# Vorlage_ATmega644PA.net
KiCad netlist of a schematic drawn in EAGLE
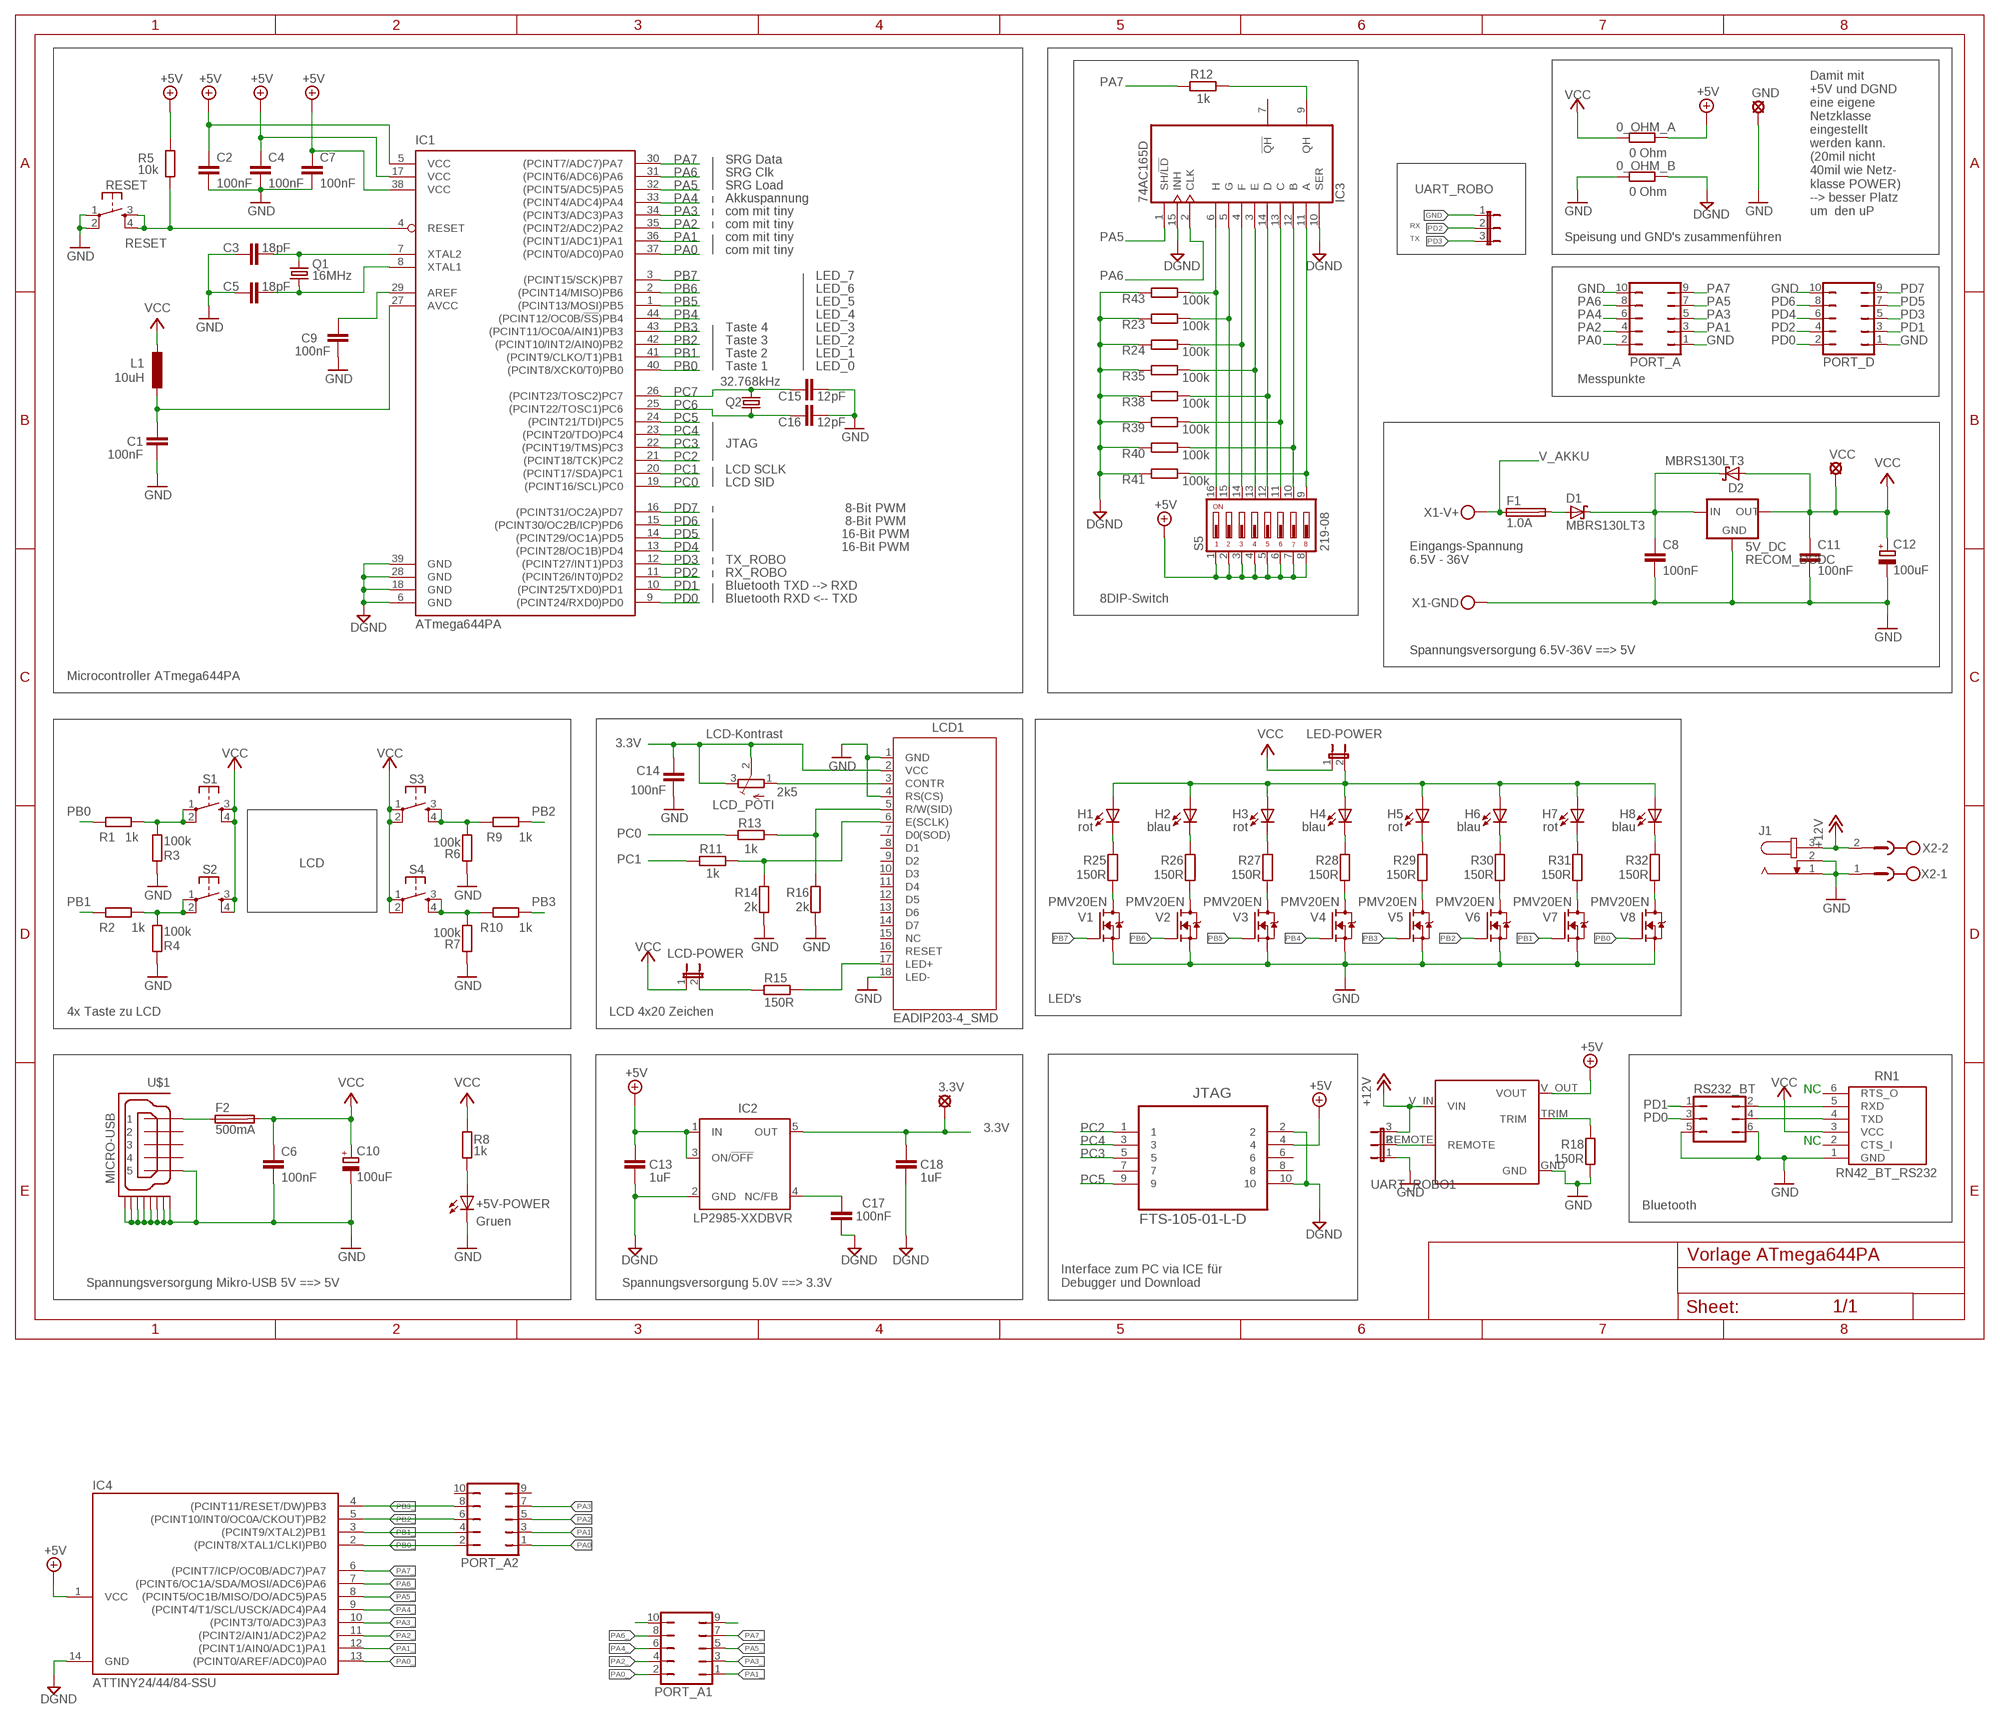
[diagram p0: schematic, sheet 1]

(export (version "E")
  (design (tool "Eeschema 10.0.6"))
  (components
    (comp (ref "+5V-POWER")
      (value "Gruen")
      (footprint "eagle-import:CHIPLED_1206")
      (libsource (lib "eagle-import") (part "LEDCHIPLED_1206"))
    )
    (comp (ref "0_OHM_A")
      (value "0 Ohm")
      (footprint "eagle-import:R0805")
      (libsource (lib "eagle-import") (part "rcl_334_R-EU_R0805"))
    )
    (comp (ref "0_OHM_B")
      (value "0 Ohm")
      (footprint "eagle-import:R0805")
      (libsource (lib "eagle-import") (part "rcl_334_R-EU_R0805"))
    )
    (comp (ref "3.3V")
      (value "3.3V")
      (footprint "eagle-import:LSP11")
      (libsource (lib "eagle-import") (part "LSP11"))
    )
    (comp (ref "5V_DC")
      (value "RECOM_DCDC")
      (footprint "eagle-import:RECOM_DCDC")
      (libsource (lib "eagle-import") (part "RECOM_DCDC"))
    )
    (comp (ref "C1")
      (value "100nF")
      (footprint "eagle-import:C0805")
      (libsource (lib "eagle-import") (part "rcl_334_C-EUC0805"))
    )
    (comp (ref "C2")
      (value "100nF")
      (footprint "eagle-import:C1206")
      (libsource (lib "eagle-import") (part "C-EUC1206"))
    )
    (comp (ref "C3")
      (value "18pF")
      (footprint "eagle-import:C0805")
      (libsource (lib "eagle-import") (part "rcl_334_C-EUC0805"))
    )
    (comp (ref "C4")
      (value "100nF")
      (footprint "eagle-import:C1206")
      (libsource (lib "eagle-import") (part "C-EUC1206"))
    )
    (comp (ref "C5")
      (value "18pF")
      (footprint "eagle-import:C0805")
      (libsource (lib "eagle-import") (part "rcl_334_C-EUC0805"))
    )
    (comp (ref "C6")
      (value "100nF")
      (footprint "eagle-import:C1206")
      (libsource (lib "eagle-import") (part "C-EUC1206"))
    )
    (comp (ref "C7")
      (value "100nF")
      (footprint "eagle-import:C0805")
      (libsource (lib "eagle-import") (part "rcl_334_C-EUC0805"))
    )
    (comp (ref "C8")
      (value "100nF")
      (footprint "eagle-import:C0805")
      (libsource (lib "eagle-import") (part "rcl_334_C-EUC0805"))
    )
    (comp (ref "C9")
      (value "100nF")
      (footprint "eagle-import:C0805")
      (libsource (lib "eagle-import") (part "rcl_334_C-EUC0805"))
    )
    (comp (ref "C10")
      (value "100uF")
      (footprint "eagle-import:UD-6,3X5,8_NICHICON")
      (libsource (lib "eagle-import") (part "CPOL-EUUD-6,3X8,8"))
    )
    (comp (ref "C11")
      (value "100nF")
      (footprint "eagle-import:C0805")
      (libsource (lib "eagle-import") (part "rcl_334_C-EUC0805"))
    )
    (comp (ref "C12")
      (value "100uF")
      (footprint "eagle-import:UD-6,3X5,8_NICHICON")
      (libsource (lib "eagle-import") (part "CPOL-EUUD-6,3X8,8"))
    )
    (comp (ref "C13")
      (value "1uF")
      (footprint "eagle-import:C0805")
      (libsource (lib "eagle-import") (part "rcl_334_C-EUC0805"))
    )
    (comp (ref "C14")
      (value "100nF")
      (footprint "eagle-import:C0805")
      (libsource (lib "eagle-import") (part "rcl_334_C-EUC0805"))
    )
    (comp (ref "C15")
      (value "12pF")
      (footprint "eagle-import:C0805")
      (libsource (lib "eagle-import") (part "rcl_334_C-EUC0805"))
    )
    (comp (ref "C16")
      (value "12pF")
      (footprint "eagle-import:C0805K")
      (libsource (lib "eagle-import") (part "C-EUC0805K"))
    )
    (comp (ref "C17")
      (value "100nF")
      (footprint "eagle-import:C0805")
      (libsource (lib "eagle-import") (part "rcl_334_C-EUC0805"))
    )
    (comp (ref "C18")
      (value "1uF")
      (footprint "eagle-import:C0805")
      (libsource (lib "eagle-import") (part "rcl_334_C-EUC0805"))
    )
    (comp (ref "D1")
      (value "MBRS130LT3")
      (footprint "eagle-import:SMB")
      (libsource (lib "eagle-import") (part "MBRS130LT3"))
    )
    (comp (ref "D2")
      (value "MBRS130LT3")
      (footprint "eagle-import:SMB")
      (libsource (lib "eagle-import") (part "MBRS130LT3"))
    )
    (comp (ref "F1")
      (value "1.0A")
      (footprint "eagle-import:F1206")
      (libsource (lib "eagle-import") (part "195601206"))
    )
    (comp (ref "F2")
      (value "500mA")
      (footprint "eagle-import:F1206")
      (libsource (lib "eagle-import") (part "195601206"))
    )
    (comp (ref "GND")
      (value "3.3V")
      (footprint "eagle-import:LSP11")
      (libsource (lib "eagle-import") (part "LSP11"))
    )
    (comp (ref "H1")
      (value "rot")
      (footprint "eagle-import:CHIPLED_1206")
      (libsource (lib "eagle-import") (part "LEDCHIPLED_1206"))
    )
    (comp (ref "H2")
      (value "blau")
      (footprint "eagle-import:CHIPLED_1206")
      (libsource (lib "eagle-import") (part "LEDCHIPLED_1206"))
    )
    (comp (ref "H3")
      (value "rot")
      (footprint "eagle-import:CHIPLED_1206")
      (libsource (lib "eagle-import") (part "LEDCHIPLED_1206"))
    )
    (comp (ref "H4")
      (value "blau")
      (footprint "eagle-import:CHIPLED_1206")
      (libsource (lib "eagle-import") (part "LEDCHIPLED_1206"))
    )
    (comp (ref "H5")
      (value "rot")
      (footprint "eagle-import:CHIPLED_1206")
      (libsource (lib "eagle-import") (part "LEDCHIPLED_1206"))
    )
    (comp (ref "H6")
      (value "blau")
      (footprint "eagle-import:CHIPLED_1206")
      (libsource (lib "eagle-import") (part "LEDCHIPLED_1206"))
    )
    (comp (ref "H7")
      (value "rot")
      (footprint "eagle-import:CHIPLED_1206")
      (libsource (lib "eagle-import") (part "LEDCHIPLED_1206"))
    )
    (comp (ref "H8")
      (value "blau")
      (footprint "eagle-import:CHIPLED_1206")
      (libsource (lib "eagle-import") (part "LEDCHIPLED_1206"))
    )
    (comp (ref "IC1")
      (value "ATmega644PA")
      (footprint "eagle-import:TQFP44")
      (fields (field (name "MPN") "ATMEGA644PV-10AU"))
      (libsource (lib "eagle-import") (part "ATMEGA644A"))
    )
    (comp (ref "IC2")
      (value "LP2985-XXDBVR")
      (footprint "eagle-import:SOT23-DBV")
      (libsource (lib "eagle-import") (part "LP2985-XXDBVR"))
    )
    (comp (ref "IC3")
      (value "74AC165D")
      (footprint "eagle-import:SO16")
      (libsource (lib "eagle-import") (part "74165DAC"))
    )
    (comp (ref "IC4")
      (value "ATTINY24/44/84-SSU")
      (footprint "eagle-import:SOIC14")
      (libsource (lib "eagle-import") (part "ATTINY24/44/84-SSU"))
    )
    (comp (ref "J1")
      (value "JACK-PLUG0")
      (footprint "eagle-import:SPC4077")
      (libsource (lib "eagle-import") (part "JACK-PLUG0"))
    )
    (comp (ref "JTAG")
      (value "FTS-105-01-L-D")
      (footprint "eagle-import:SAMTEC_FTS-105-01-L-D")
      (libsource (lib "eagle-import") (part "FTS-105-01-L-D"))
    )
    (comp (ref "L1")
      (value "10uH")
      (footprint "eagle-import:L2825P")
      (libsource (lib "eagle-import") (part "L-EUL2825P"))
    )
    (comp (ref "LCD-POWER")
      (value "JP1E")
      (footprint "eagle-import:JP1")
      (libsource (lib "eagle-import") (part "JP1E"))
    )
    (comp (ref "LCD1")
      (value "EADIP203-4_SMD")
      (footprint "eagle-import:EADIP203-4SMD")
      (libsource (lib "eagle-import") (part "EADIP203-4EADIP203-4SMD"))
    )
    (comp (ref "LCD_POTI")
      (value "2k5")
      (footprint "eagle-import:3223G")
      (libsource (lib "eagle-import") (part "TRIM_EU-3223G"))
    )
    (comp (ref "LED-POWER")
      (value "JP1E")
      (footprint "eagle-import:JP1")
      (libsource (lib "eagle-import") (part "JP1E"))
    )
    (comp (ref "PORT_A")
      (value "JP5Q")
      (footprint "eagle-import:JP5Q")
      (libsource (lib "eagle-import") (part "JP5Q"))
    )
    (comp (ref "PORT_A1")
      (value "JP5Q")
      (footprint "eagle-import:JP5Q")
      (libsource (lib "eagle-import") (part "JP5Q"))
    )
    (comp (ref "PORT_A2")
      (value "JP5Q")
      (footprint "eagle-import:JP5Q")
      (libsource (lib "eagle-import") (part "JP5Q"))
    )
    (comp (ref "PORT_D")
      (value "JP5Q")
      (footprint "eagle-import:JP5Q")
      (libsource (lib "eagle-import") (part "JP5Q"))
    )
    (comp (ref "Q1")
      (value "16MHz")
      (footprint "eagle-import:HC49UP")
      (libsource (lib "eagle-import") (part "CRYSTALHC49UP"))
    )
    (comp (ref "Q2")
      (value "32.768kHz")
      (footprint "eagle-import:TC38H")
      (libsource (lib "eagle-import") (part "CRYSTALTC38H"))
    )
    (comp (ref "R1")
      (value "1k")
      (footprint "eagle-import:R0805")
      (libsource (lib "eagle-import") (part "rcl_334_R-EU_R0805"))
    )
    (comp (ref "R2")
      (value "1k")
      (footprint "eagle-import:R0805")
      (libsource (lib "eagle-import") (part "rcl_334_R-EU_R0805"))
    )
    (comp (ref "R3")
      (value "100k")
      (footprint "eagle-import:R0805")
      (libsource (lib "eagle-import") (part "rcl_334_R-EU_R0805"))
    )
    (comp (ref "R4")
      (value "100k")
      (footprint "eagle-import:R0805")
      (libsource (lib "eagle-import") (part "rcl_334_R-EU_R0805"))
    )
    (comp (ref "R5")
      (value "10k")
      (footprint "eagle-import:R0805")
      (libsource (lib "eagle-import") (part "rcl_334_R-EU_R0805"))
    )
    (comp (ref "R6")
      (value "100k")
      (footprint "eagle-import:R0805")
      (libsource (lib "eagle-import") (part "rcl_334_R-EU_R0805"))
    )
    (comp (ref "R7")
      (value "100k")
      (footprint "eagle-import:R0805")
      (libsource (lib "eagle-import") (part "rcl_334_R-EU_R0805"))
    )
    (comp (ref "R8")
      (value "1k")
      (footprint "eagle-import:R0805")
      (libsource (lib "eagle-import") (part "rcl_334_R-EU_R0805"))
    )
    (comp (ref "R9")
      (value "1k")
      (footprint "eagle-import:R0805")
      (libsource (lib "eagle-import") (part "rcl_334_R-EU_R0805"))
    )
    (comp (ref "R10")
      (value "1k")
      (footprint "eagle-import:R0805")
      (libsource (lib "eagle-import") (part "rcl_334_R-EU_R0805"))
    )
    (comp (ref "R11")
      (value "1k")
      (footprint "eagle-import:R0805")
      (libsource (lib "eagle-import") (part "rcl_334_R-EU_R0805"))
    )
    (comp (ref "R12")
      (value "1k")
      (footprint "eagle-import:R1206")
      (libsource (lib "eagle-import") (part "R-EU_R1206"))
    )
    (comp (ref "R13")
      (value "1k")
      (footprint "eagle-import:R0805")
      (libsource (lib "eagle-import") (part "rcl_334_R-EU_R0805"))
    )
    (comp (ref "R14")
      (value "2k")
      (footprint "eagle-import:R0805")
      (libsource (lib "eagle-import") (part "rcl_334_R-EU_R0805"))
    )
    (comp (ref "R15")
      (value "150R")
      (footprint "eagle-import:R1206")
      (libsource (lib "eagle-import") (part "R-EU_R1206"))
    )
    (comp (ref "R16")
      (value "2k")
      (footprint "eagle-import:R0805")
      (libsource (lib "eagle-import") (part "rcl_334_R-EU_R0805"))
    )
    (comp (ref "R18")
      (value "150R")
      (footprint "eagle-import:R0805")
      (libsource (lib "eagle-import") (part "rcl_334_R-EU_R0805"))
    )
    (comp (ref "R23")
      (value "100k")
      (footprint "eagle-import:R0805")
      (libsource (lib "eagle-import") (part "rcl_334_R-EU_R0805"))
    )
    (comp (ref "R24")
      (value "100k")
      (footprint "eagle-import:R0805")
      (libsource (lib "eagle-import") (part "rcl_334_R-EU_R0805"))
    )
    (comp (ref "R25")
      (value "150R")
      (footprint "eagle-import:R0805")
      (libsource (lib "eagle-import") (part "rcl_334_R-EU_R0805"))
    )
    (comp (ref "R26")
      (value "150R")
      (footprint "eagle-import:R0805")
      (libsource (lib "eagle-import") (part "rcl_334_R-EU_R0805"))
    )
    (comp (ref "R27")
      (value "150R")
      (footprint "eagle-import:R0805")
      (libsource (lib "eagle-import") (part "rcl_334_R-EU_R0805"))
    )
    (comp (ref "R28")
      (value "150R")
      (footprint "eagle-import:R0805")
      (libsource (lib "eagle-import") (part "rcl_334_R-EU_R0805"))
    )
    (comp (ref "R29")
      (value "150R")
      (footprint "eagle-import:R0805")
      (libsource (lib "eagle-import") (part "rcl_334_R-EU_R0805"))
    )
    (comp (ref "R30")
      (value "150R")
      (footprint "eagle-import:R0805")
      (libsource (lib "eagle-import") (part "rcl_334_R-EU_R0805"))
    )
    (comp (ref "R31")
      (value "150R")
      (footprint "eagle-import:R0805")
      (libsource (lib "eagle-import") (part "rcl_334_R-EU_R0805"))
    )
    (comp (ref "R32")
      (value "150R")
      (footprint "eagle-import:R0805")
      (libsource (lib "eagle-import") (part "rcl_334_R-EU_R0805"))
    )
    (comp (ref "R35")
      (value "100k")
      (footprint "eagle-import:R0805")
      (libsource (lib "eagle-import") (part "rcl_334_R-EU_R0805"))
    )
    (comp (ref "R38")
      (value "100k")
      (footprint "eagle-import:R0805")
      (libsource (lib "eagle-import") (part "rcl_334_R-EU_R0805"))
    )
    (comp (ref "R39")
      (value "100k")
      (footprint "eagle-import:R0805")
      (libsource (lib "eagle-import") (part "rcl_334_R-EU_R0805"))
    )
    (comp (ref "R40")
      (value "100k")
      (footprint "eagle-import:R0805")
      (libsource (lib "eagle-import") (part "rcl_334_R-EU_R0805"))
    )
    (comp (ref "R41")
      (value "100k")
      (footprint "eagle-import:R0805")
      (libsource (lib "eagle-import") (part "rcl_334_R-EU_R0805"))
    )
    (comp (ref "R43")
      (value "100k")
      (footprint "eagle-import:R0805")
      (libsource (lib "eagle-import") (part "rcl_334_R-EU_R0805"))
    )
    (comp (ref "RESET")
      (value "TS42_4PAD")
      (footprint "eagle-import:TS42_4PAD")
      (libsource (lib "eagle-import") (part "TS42_4PAD"))
    )
    (comp (ref "RN1")
      (value "RN42_BT_RS232")
      (footprint "eagle-import:RN42BT_RS232")
      (libsource (lib "eagle-import") (part "RN42_BT_RS232"))
    )
    (comp (ref "RS232_BT")
      (value "JP3Q")
      (footprint "eagle-import:JP3Q")
      (libsource (lib "eagle-import") (part "JP3Q"))
    )
    (comp (ref "S1")
      (value "TS42_4PAD")
      (footprint "eagle-import:TS42_4PAD")
      (libsource (lib "eagle-import") (part "TS42_4PAD"))
    )
    (comp (ref "S2")
      (value "TS42_4PAD")
      (footprint "eagle-import:TS42_4PAD")
      (libsource (lib "eagle-import") (part "TS42_4PAD"))
    )
    (comp (ref "S3")
      (value "TS42_4PAD")
      (footprint "eagle-import:TS42_4PAD")
      (libsource (lib "eagle-import") (part "TS42_4PAD"))
    )
    (comp (ref "S4")
      (value "TS42_4PAD")
      (footprint "eagle-import:TS42_4PAD")
      (libsource (lib "eagle-import") (part "TS42_4PAD"))
    )
    (comp (ref "S5")
      (value "219-08")
      (footprint "eagle-import:CTS-219-08")
      (libsource (lib "eagle-import") (part "219-08"))
    )
    (comp (ref "U$1")
      (value "MICRO-USB")
      (footprint "eagle-import:47589-0001")
      (libsource (lib "eagle-import") (part "MICRO-USB-RECEPTACLE47589-0001"))
    )
    (comp (ref "U$3")
      (value "DCDC")
      (footprint "eagle-import:1X2,3_2.54MM")
      (libsource (lib "eagle-import") (part "DCDC"))
    )
    (comp (ref "UART_ROBO")
      (value "JP2E")
      (footprint "eagle-import:JP2")
      (libsource (lib "eagle-import") (part "JP2E"))
    )
    (comp (ref "UART_ROBO1")
      (value "JP2E")
      (footprint "eagle-import:JP2")
      (libsource (lib "eagle-import") (part "JP2E"))
    )
    (comp (ref "V1")
      (value "PMV20EN")
      (footprint "eagle-import:SOT23")
      (libsource (lib "eagle-import") (part "BSS138"))
    )
    (comp (ref "V2")
      (value "PMV20EN")
      (footprint "eagle-import:SOT23")
      (libsource (lib "eagle-import") (part "BSS138"))
    )
    (comp (ref "V3")
      (value "PMV20EN")
      (footprint "eagle-import:SOT23")
      (libsource (lib "eagle-import") (part "BSS138"))
    )
    (comp (ref "V4")
      (value "PMV20EN")
      (footprint "eagle-import:SOT23")
      (libsource (lib "eagle-import") (part "BSS138"))
    )
    (comp (ref "V5")
      (value "PMV20EN")
      (footprint "eagle-import:SOT23")
      (libsource (lib "eagle-import") (part "BSS138"))
    )
    (comp (ref "V6")
      (value "PMV20EN")
      (footprint "eagle-import:SOT23")
      (libsource (lib "eagle-import") (part "BSS138"))
    )
    (comp (ref "V7")
      (value "PMV20EN")
      (footprint "eagle-import:SOT23")
      (libsource (lib "eagle-import") (part "BSS138"))
    )
    (comp (ref "V8")
      (value "PMV20EN")
      (footprint "eagle-import:SOT23")
      (libsource (lib "eagle-import") (part "BSS138"))
    )
    (comp (ref "VCC")
      (value "3.3V")
      (footprint "eagle-import:LSP11")
      (libsource (lib "eagle-import") (part "LSP11"))
    )
    (comp (ref "X1")
      (value "MKDSN1,5/2-5,08")
      (footprint "eagle-import:MKDSN1,5_2-5,08")
      (fields (field (name "MPN") "MKDSN 1,5/2-5.08"))
      (libsource (lib "eagle-import") (part "MKDSN1,5/2-5,08"))
    )
    (comp (ref "X2")
      (value "MSTBV2")
      (footprint "eagle-import:MSTBV2")
      (libsource (lib "eagle-import") (part "MSTBV2"))
    )
  )
  (nets
    (net (code "1") (name "+5V") (class "Default")
      (node (ref "0_OHM_A") (pin "2") (pinfunction "2_2") (pintype "passive"))
      (node (ref "C13") (pin "1") (pinfunction "1_1") (pintype "passive"))
      (node (ref "C2") (pin "1") (pinfunction "1_1") (pintype "passive"))
      (node (ref "C4") (pin "1") (pinfunction "1_1") (pintype "passive"))
      (node (ref "C7") (pin "1") (pinfunction "1_1") (pintype "passive"))
      (node (ref "IC1") (pin "17") (pinfunction "VCC_17") (pintype "power_in"))
      (node (ref "IC1") (pin "38") (pinfunction "VCC_38") (pintype "power_in"))
      (node (ref "IC1") (pin "5") (pinfunction "VCC_5") (pintype "power_in"))
      (node (ref "IC2") (pin "1") (pinfunction "IN_1") (pintype "input"))
      (node (ref "IC2") (pin "3") (pinfunction "ON/~{OFF}_3") (pintype "input"))
      (node (ref "IC4") (pin "1") (pinfunction "VCC_1") (pintype "power_in"))
      (node (ref "JTAG") (pin "4") (pinfunction "4_4") (pintype "passive"))
      (node (ref "R5") (pin "2") (pinfunction "2_2") (pintype "passive"))
      (node (ref "S5") (pin "1") (pinfunction "1_1") (pintype "passive"))
      (node (ref "S5") (pin "2") (pinfunction "2_2") (pintype "passive"))
      (node (ref "S5") (pin "3") (pinfunction "3_3") (pintype "passive"))
      (node (ref "S5") (pin "4") (pinfunction "4_4") (pintype "passive"))
      (node (ref "S5") (pin "5") (pinfunction "5_5") (pintype "passive"))
      (node (ref "S5") (pin "6") (pinfunction "6_6") (pintype "passive"))
      (node (ref "S5") (pin "7") (pinfunction "7_7") (pintype "passive"))
      (node (ref "S5") (pin "8") (pinfunction "8_8") (pintype "passive"))
      (node (ref "U$3") (pin "V_OUT") (pinfunction "VOUT_V_OUT") (pintype "bidirectional"))
    )
    (net (code "2") (name "+12V") (class "Default")
      (node (ref "J1") (pin "3") (pinfunction "3_3") (pintype "passive"))
      (node (ref "U$3") (pin "V_IN") (pinfunction "VIN_V_IN") (pintype "bidirectional"))
      (node (ref "UART_ROBO1") (pin "3") (pinfunction "3_3") (pintype "passive"))
      (node (ref "X2") (pin "2") (pinfunction "SK_2") (pintype "passive"))
    )
    (net (code "3") (name "/3.3V") (class "Default")
      (node (ref "3.3V") (pin "MP") (pinfunction "MP_MP") (pintype "passive"))
      (node (ref "C14") (pin "1") (pinfunction "1_1") (pintype "passive"))
      (node (ref "C18") (pin "1") (pinfunction "1_1") (pintype "passive"))
      (node (ref "IC2") (pin "5") (pinfunction "OUT_5") (pintype "passive"))
      (node (ref "LCD1") (pin "2") (pinfunction "VCC_2") (pintype "passive"))
      (node (ref "LCD_POTI") (pin "2") (pinfunction "S_2") (pintype "passive"))
      (node (ref "LCD_POTI") (pin "3") (pinfunction "E_3") (pintype "passive"))
    )
    (net (code "4") (name "/PA4") (class "Default")
      (node (ref "IC1") (pin "33") (pinfunction "(PCINT4/ADC4)PA4_33") (pintype "bidirectional"))
      (node (ref "PORT_A") (pin "6") (pinfunction "6_6") (pintype "passive"))
    )
    (net (code "5") (name "/PA5") (class "Default")
      (node (ref "IC1") (pin "32") (pinfunction "(PCINT5/ADC5)PA5_32") (pintype "bidirectional"))
      (node (ref "IC3") (pin "1") (pinfunction "SH/~{LD}_1") (pintype "input"))
      (node (ref "PORT_A") (pin "7") (pinfunction "7_7") (pintype "passive"))
    )
    (net (code "6") (name "/PA6") (class "Default")
      (node (ref "IC1") (pin "31") (pinfunction "(PCINT6/ADC6)PA6_31") (pintype "bidirectional"))
      (node (ref "IC3") (pin "2") (pinfunction "CLK_2") (pintype "input"))
      (node (ref "PORT_A") (pin "8") (pinfunction "8_8") (pintype "passive"))
    )
    (net (code "7") (name "/PA7") (class "Default")
      (node (ref "IC1") (pin "30") (pinfunction "(PCINT7/ADC7)PA7_30") (pintype "bidirectional"))
      (node (ref "PORT_A") (pin "9") (pinfunction "9_9") (pintype "passive"))
      (node (ref "R12") (pin "2") (pinfunction "2_2") (pintype "passive"))
    )
    (net (code "8") (name "/PC0") (class "Default")
      (node (ref "IC1") (pin "19") (pinfunction "(PCINT16/SCL)PC0_19") (pintype "output"))
      (node (ref "R13") (pin "2") (pinfunction "2_2") (pintype "passive"))
    )
    (net (code "9") (name "/PC1") (class "Default")
      (node (ref "IC1") (pin "20") (pinfunction "(PCINT17/SDA)PC1_20") (pintype "output"))
      (node (ref "R11") (pin "2") (pinfunction "2_2") (pintype "passive"))
    )
    (net (code "10") (name "/PC2") (class "Default")
      (node (ref "IC1") (pin "21") (pinfunction "(PCINT18/TCK)PC2_21") (pintype "output"))
      (node (ref "JTAG") (pin "1") (pinfunction "1_1") (pintype "passive"))
    )
    (net (code "11") (name "/PC3") (class "Default")
      (node (ref "IC1") (pin "22") (pinfunction "(PCINT19/TMS)PC3_22") (pintype "output"))
      (node (ref "JTAG") (pin "5") (pinfunction "5_5") (pintype "passive"))
    )
    (net (code "12") (name "/PC4") (class "Default")
      (node (ref "IC1") (pin "23") (pinfunction "(PCINT20/TDO)PC4_23") (pintype "output"))
      (node (ref "JTAG") (pin "3") (pinfunction "3_3") (pintype "passive"))
    )
    (net (code "13") (name "/PC5") (class "Default")
      (node (ref "IC1") (pin "24") (pinfunction "(PCINT21/TDI)PC5_24") (pintype "output"))
      (node (ref "JTAG") (pin "9") (pinfunction "9_9") (pintype "passive"))
    )
    (net (code "14") (name "/PC6") (class "Default")
      (node (ref "C16") (pin "1") (pinfunction "1_1") (pintype "passive"))
      (node (ref "IC1") (pin "25") (pinfunction "(PCINT22/TOSC1)PC6_25") (pintype "output"))
      (node (ref "Q2") (pin "2") (pinfunction "2_2") (pintype "passive"))
    )
    (net (code "15") (name "/PC7") (class "Default")
      (node (ref "C15") (pin "1") (pinfunction "1_1") (pintype "passive"))
      (node (ref "IC1") (pin "26") (pinfunction "(PCINT23/TOSC2)PC7_26") (pintype "output"))
      (node (ref "Q2") (pin "1") (pinfunction "1_1") (pintype "passive"))
    )
    (net (code "16") (name "/PD0") (class "Default")
      (node (ref "IC1") (pin "9") (pinfunction "(PCINT24/RXD0)PD0_9") (pintype "bidirectional"))
      (node (ref "PORT_D") (pin "2") (pinfunction "2_2") (pintype "passive"))
      (node (ref "RS232_BT") (pin "3") (pinfunction "3_3") (pintype "passive"))
    )
    (net (code "17") (name "/PD1") (class "Default")
      (node (ref "IC1") (pin "10") (pinfunction "(PCINT25/TXD0)PD1_10") (pintype "bidirectional"))
      (node (ref "PORT_D") (pin "3") (pinfunction "3_3") (pintype "passive"))
      (node (ref "RS232_BT") (pin "1") (pinfunction "1_1") (pintype "passive"))
    )
    (net (code "18") (name "/PD4") (class "Default")
      (node (ref "IC1") (pin "13") (pinfunction "(PCINT28/OC1B)PD4_13") (pintype "bidirectional"))
      (node (ref "PORT_D") (pin "6") (pinfunction "6_6") (pintype "passive"))
    )
    (net (code "19") (name "/PD5") (class "Default")
      (node (ref "IC1") (pin "14") (pinfunction "(PCINT29/OC1A)PD5_14") (pintype "bidirectional"))
      (node (ref "PORT_D") (pin "7") (pinfunction "7_7") (pintype "passive"))
    )
    (net (code "20") (name "/PD6") (class "Default")
      (node (ref "IC1") (pin "15") (pinfunction "(PCINT30/OC2B/ICP)PD6_15") (pintype "bidirectional"))
      (node (ref "PORT_D") (pin "8") (pinfunction "8_8") (pintype "passive"))
    )
    (net (code "21") (name "/PD7") (class "Default")
      (node (ref "IC1") (pin "16") (pinfunction "(PCINT31/OC2A)PD7_16") (pintype "bidirectional"))
      (node (ref "PORT_D") (pin "9") (pinfunction "9_9") (pintype "passive"))
    )
    (net (code "22") (name "/RESET") (class "Default")
      (node (ref "IC1") (pin "4") (pinfunction "RESET_4") (pintype "input"))
      (node (ref "R5") (pin "1") (pinfunction "1_1") (pintype "passive"))
      (node (ref "RESET") (pin "3") (pinfunction "3_3") (pintype "passive"))
      (node (ref "RESET") (pin "4") (pinfunction "4_4") (pintype "passive"))
    )
    (net (code "23") (name "/V_AKKU") (class "Default")
      (node (ref "F1") (pin "1") (pinfunction "1_1") (pintype "passive"))
      (node (ref "X1") (pin "2.1") (pinfunction "KL_2.1") (pintype "passive"))
      (node (ref "X1") (pin "2.2") (pinfunction "KL_2.2") (pintype "passive"))
    )
    (net (code "24") (name "DGND") (class "Default")
      (node (ref "0_OHM_B") (pin "2") (pinfunction "2_2") (pintype "passive"))
      (node (ref "C13") (pin "2") (pinfunction "2_2") (pintype "passive"))
      (node (ref "C17") (pin "2") (pinfunction "2_2") (pintype "passive"))
      (node (ref "C18") (pin "2") (pinfunction "2_2") (pintype "passive"))
      (node (ref "IC1") (pin "18") (pinfunction "GND_18") (pintype "power_in"))
      (node (ref "IC1") (pin "28") (pinfunction "GND_28") (pintype "power_in"))
      (node (ref "IC1") (pin "39") (pinfunction "GND_39") (pintype "power_in"))
      (node (ref "IC1") (pin "6") (pinfunction "GND_6") (pintype "power_in"))
      (node (ref "IC2") (pin "2") (pinfunction "GND_2") (pintype "power_in"))
      (node (ref "IC3") (pin "10") (pinfunction "SER_10") (pintype "input"))
      (node (ref "IC3") (pin "15") (pinfunction "INH_15") (pintype "input"))
      (node (ref "IC4") (pin "14") (pinfunction "GND_14") (pintype "power_in"))
      (node (ref "JTAG") (pin "10") (pinfunction "10_10") (pintype "passive"))
      (node (ref "JTAG") (pin "2") (pinfunction "2_2") (pintype "passive"))
      (node (ref "R23") (pin "2") (pinfunction "2_2") (pintype "passive"))
      (node (ref "R24") (pin "2") (pinfunction "2_2") (pintype "passive"))
      (node (ref "R35") (pin "2") (pinfunction "2_2") (pintype "passive"))
      (node (ref "R38") (pin "2") (pinfunction "2_2") (pintype "passive"))
      (node (ref "R39") (pin "2") (pinfunction "2_2") (pintype "passive"))
      (node (ref "R40") (pin "2") (pinfunction "2_2") (pintype "passive"))
      (node (ref "R41") (pin "2") (pinfunction "2_2") (pintype "passive"))
      (node (ref "R43") (pin "2") (pinfunction "2_2") (pintype "passive"))
    )
    (net (code "25") (name "GND") (class "Default")
      (node (ref "+5V-POWER") (pin "C") (pinfunction "C_C") (pintype "passive"))
      (node (ref "0_OHM_B") (pin "1") (pinfunction "1_1") (pintype "passive"))
      (node (ref "5V_DC") (pin "GND") (pinfunction "GND_GND") (pintype "input"))
      (node (ref "C1") (pin "1") (pinfunction "1_1") (pintype "passive"))
      (node (ref "C10") (pin "-") (pinfunction "-_-") (pintype "passive"))
      (node (ref "C11") (pin "2") (pinfunction "2_2") (pintype "passive"))
      (node (ref "C12") (pin "-") (pinfunction "-_-") (pintype "passive"))
      (node (ref "C14") (pin "2") (pinfunction "2_2") (pintype "passive"))
      (node (ref "C15") (pin "2") (pinfunction "2_2") (pintype "passive"))
      (node (ref "C16") (pin "2") (pinfunction "2_2") (pintype "passive"))
      (node (ref "C2") (pin "2") (pinfunction "2_2") (pintype "passive"))
      (node (ref "C3") (pin "1") (pinfunction "1_1") (pintype "passive"))
      (node (ref "C4") (pin "2") (pinfunction "2_2") (pintype "passive"))
      (node (ref "C5") (pin "2") (pinfunction "2_2") (pintype "passive"))
      (node (ref "C6") (pin "2") (pinfunction "2_2") (pintype "passive"))
      (node (ref "C7") (pin "2") (pinfunction "2_2") (pintype "passive"))
      (node (ref "C8") (pin "2") (pinfunction "2_2") (pintype "passive"))
      (node (ref "C9") (pin "1") (pinfunction "1_1") (pintype "passive"))
      (node (ref "GND") (pin "MP") (pinfunction "MP_MP") (pintype "passive"))
      (node (ref "J1") (pin "1") (pinfunction "1_1") (pintype "passive"))
      (node (ref "J1") (pin "2") (pinfunction "2_2") (pintype "passive"))
      (node (ref "LCD1") (pin "1") (pinfunction "GND_1") (pintype "power_in"))
      (node (ref "LCD1") (pin "18") (pinfunction "LED-_18") (pintype "passive"))
      (node (ref "LCD1") (pin "4") (pinfunction "RS(CS)_4") (pintype "input"))
      (node (ref "PORT_A") (pin "1") (pinfunction "1_1") (pintype "passive"))
      (node (ref "PORT_A") (pin "10") (pinfunction "10_10") (pintype "passive"))
      (node (ref "PORT_D") (pin "1") (pinfunction "1_1") (pintype "passive"))
      (node (ref "PORT_D") (pin "10") (pinfunction "10_10") (pintype "passive"))
      (node (ref "R14") (pin "1") (pinfunction "1_1") (pintype "passive"))
      (node (ref "R16") (pin "1") (pinfunction "1_1") (pintype "passive"))
      (node (ref "R18") (pin "1") (pinfunction "1_1") (pintype "passive"))
      (node (ref "R3") (pin "1") (pinfunction "1_1") (pintype "passive"))
      (node (ref "R4") (pin "1") (pinfunction "1_1") (pintype "passive"))
      (node (ref "R6") (pin "2") (pinfunction "2_2") (pintype "passive"))
      (node (ref "R7") (pin "2") (pinfunction "2_2") (pintype "passive"))
      (node (ref "RESET") (pin "1") (pinfunction "1_1") (pintype "passive"))
      (node (ref "RESET") (pin "2") (pinfunction "2_2") (pintype "passive"))
      (node (ref "RN1") (pin "1") (pinfunction "GND_1") (pintype "bidirectional"))
      (node (ref "RS232_BT") (pin "5") (pinfunction "5_5") (pintype "passive"))
      (node (ref "RS232_BT") (pin "6") (pinfunction "6_6") (pintype "passive"))
      (node (ref "U$1") (pin "5") (pinfunction "5_5") (pintype "input"))
      (node (ref "U$1") (pin "CASING1") (pinfunction "GND1_CASING1") (pintype "bidirectional"))
      (node (ref "U$1") (pin "CASING2") (pinfunction "GND2_CASING2") (pintype "bidirectional"))
      (node (ref "U$1") (pin "CASING3") (pinfunction "GND3_CASING3") (pintype "bidirectional"))
      (node (ref "U$1") (pin "CASING4") (pinfunction "GND4_CASING4") (pintype "bidirectional"))
      (node (ref "U$1") (pin "CASING5") (pinfunction "GND5_CASING5") (pintype "bidirectional"))
      (node (ref "U$1") (pin "CASING6") (pinfunction "GND6_CASING6") (pintype "bidirectional"))
      (node (ref "U$1") (pin "CASING7") (pinfunction "GND7_CASING7") (pintype "bidirectional"))
      (node (ref "U$1") (pin "CASING8") (pinfunction "GND8_CASING8") (pintype "bidirectional"))
      (node (ref "U$3") (pin "GND") (pinfunction "GND_GND") (pintype "bidirectional"))
      (node (ref "UART_ROBO") (pin "1") (pinfunction "1_1") (pintype "passive"))
      (node (ref "UART_ROBO1") (pin "1") (pinfunction "1_1") (pintype "passive"))
      (node (ref "V1") (pin "2") (pinfunction "S_2") (pintype "passive"))
      (node (ref "V2") (pin "2") (pinfunction "S_2") (pintype "passive"))
      (node (ref "V3") (pin "2") (pinfunction "S_2") (pintype "passive"))
      (node (ref "V4") (pin "2") (pinfunction "S_2") (pintype "passive"))
      (node (ref "V5") (pin "2") (pinfunction "S_2") (pintype "passive"))
      (node (ref "V6") (pin "2") (pinfunction "S_2") (pintype "passive"))
      (node (ref "V7") (pin "2") (pinfunction "S_2") (pintype "passive"))
      (node (ref "V8") (pin "2") (pinfunction "S_2") (pintype "passive"))
      (node (ref "X1") (pin "1.1") (pinfunction "KL_1.1") (pintype "passive"))
      (node (ref "X1") (pin "1.2") (pinfunction "KL_1.2") (pintype "passive"))
      (node (ref "X2") (pin "1") (pinfunction "SK_1") (pintype "passive"))
    )
    (net (code "26") (name "Net-(+5V-POWER-PadA)") (class "Default")
      (node (ref "+5V-POWER") (pin "A") (pinfunction "A_A") (pintype "passive"))
      (node (ref "R8") (pin "1") (pinfunction "1_1") (pintype "passive"))
    )
    (net (code "27") (name "Net-(5V_DC-PadIN)") (class "Default")
      (node (ref "5V_DC") (pin "IN") (pinfunction "IN_IN") (pintype "input"))
      (node (ref "C8") (pin "1") (pinfunction "1_1") (pintype "passive"))
      (node (ref "D1") (pin "C") (pinfunction "C_C") (pintype "passive"))
      (node (ref "D2") (pin "C") (pinfunction "C_C") (pintype "passive"))
    )
    (net (code "28") (name "Net-(D1-PadA)") (class "Default")
      (node (ref "D1") (pin "A") (pinfunction "A_A") (pintype "passive"))
      (node (ref "F1") (pin "2") (pinfunction "2_2") (pintype "passive"))
    )
    (net (code "29") (name "Net-(F2-Pad1)") (class "Default")
      (node (ref "F2") (pin "1") (pinfunction "1_1") (pintype "passive"))
      (node (ref "U$1") (pin "1") (pinfunction "1_1") (pintype "input"))
    )
    (net (code "30") (name "Net-(H1-PadA)") (class "Default")
      (node (ref "H1") (pin "A") (pinfunction "A_A") (pintype "passive"))
      (node (ref "H2") (pin "A") (pinfunction "A_A") (pintype "passive"))
      (node (ref "H3") (pin "A") (pinfunction "A_A") (pintype "passive"))
      (node (ref "H4") (pin "A") (pinfunction "A_A") (pintype "passive"))
      (node (ref "H5") (pin "A") (pinfunction "A_A") (pintype "passive"))
      (node (ref "H6") (pin "A") (pinfunction "A_A") (pintype "passive"))
      (node (ref "H7") (pin "A") (pinfunction "A_A") (pintype "passive"))
      (node (ref "H8") (pin "A") (pinfunction "A_A") (pintype "passive"))
      (node (ref "LED-POWER") (pin "2") (pinfunction "2_2") (pintype "passive"))
    )
    (net (code "31") (name "Net-(H1-PadC)") (class "Default")
      (node (ref "H1") (pin "C") (pinfunction "C_C") (pintype "passive"))
      (node (ref "R25") (pin "2") (pinfunction "2_2") (pintype "passive"))
    )
    (net (code "32") (name "Net-(H2-PadC)") (class "Default")
      (node (ref "H2") (pin "C") (pinfunction "C_C") (pintype "passive"))
      (node (ref "R26") (pin "2") (pinfunction "2_2") (pintype "passive"))
    )
    (net (code "33") (name "Net-(H3-PadC)") (class "Default")
      (node (ref "H3") (pin "C") (pinfunction "C_C") (pintype "passive"))
      (node (ref "R27") (pin "2") (pinfunction "2_2") (pintype "passive"))
    )
    (net (code "34") (name "Net-(H4-PadC)") (class "Default")
      (node (ref "H4") (pin "C") (pinfunction "C_C") (pintype "passive"))
      (node (ref "R28") (pin "2") (pinfunction "2_2") (pintype "passive"))
    )
    (net (code "35") (name "Net-(H5-PadC)") (class "Default")
      (node (ref "H5") (pin "C") (pinfunction "C_C") (pintype "passive"))
      (node (ref "R29") (pin "2") (pinfunction "2_2") (pintype "passive"))
    )
    (net (code "36") (name "Net-(H6-PadC)") (class "Default")
      (node (ref "H6") (pin "C") (pinfunction "C_C") (pintype "passive"))
      (node (ref "R30") (pin "2") (pinfunction "2_2") (pintype "passive"))
    )
    (net (code "37") (name "Net-(H7-PadC)") (class "Default")
      (node (ref "H7") (pin "C") (pinfunction "C_C") (pintype "passive"))
      (node (ref "R31") (pin "2") (pinfunction "2_2") (pintype "passive"))
    )
    (net (code "38") (name "Net-(H8-PadC)") (class "Default")
      (node (ref "H8") (pin "C") (pinfunction "C_C") (pintype "passive"))
      (node (ref "R32") (pin "2") (pinfunction "2_2") (pintype "passive"))
    )
    (net (code "39") (name "Net-(IC1-AREF)") (class "Default")
      (node (ref "C9") (pin "2") (pinfunction "2_2") (pintype "passive"))
      (node (ref "IC1") (pin "29") (pinfunction "AREF_29") (pintype "passive"))
    )
    (net (code "40") (name "Net-(IC1-AVCC)") (class "Default")
      (node (ref "C1") (pin "2") (pinfunction "2_2") (pintype "passive"))
      (node (ref "IC1") (pin "27") (pinfunction "AVCC_27") (pintype "passive"))
      (node (ref "L1") (pin "2") (pinfunction "2_2") (pintype "passive"))
    )
    (net (code "41") (name "Net-(IC1-XTAL1)") (class "Default")
      (node (ref "C5") (pin "1") (pinfunction "1_1") (pintype "passive"))
      (node (ref "IC1") (pin "8") (pinfunction "XTAL1_8") (pintype "bidirectional"))
      (node (ref "Q1") (pin "1") (pinfunction "1_1") (pintype "passive"))
    )
    (net (code "42") (name "Net-(IC1-XTAL2)") (class "Default")
      (node (ref "C3") (pin "2") (pinfunction "2_2") (pintype "passive"))
      (node (ref "IC1") (pin "7") (pinfunction "XTAL2_7") (pintype "bidirectional"))
      (node (ref "Q1") (pin "2") (pinfunction "2_2") (pintype "passive"))
    )
    (net (code "43") (name "Net-(IC2-NC{slash}FB)") (class "Default")
      (node (ref "C17") (pin "1") (pinfunction "1_1") (pintype "passive"))
      (node (ref "IC2") (pin "4") (pinfunction "NC/FB_4") (pintype "passive"))
    )
    (net (code "44") (name "Net-(IC3A-A)") (class "Default")
      (node (ref "IC3") (pin "11") (pinfunction "A_11") (pintype "input"))
      (node (ref "R41") (pin "1") (pinfunction "1_1") (pintype "passive"))
      (node (ref "S5") (pin "9") (pinfunction "9_9") (pintype "passive"))
    )
    (net (code "45") (name "Net-(IC3A-B)") (class "Default")
      (node (ref "IC3") (pin "12") (pinfunction "B_12") (pintype "input"))
      (node (ref "R40") (pin "1") (pinfunction "1_1") (pintype "passive"))
      (node (ref "S5") (pin "10") (pinfunction "10_10") (pintype "passive"))
    )
    (net (code "46") (name "Net-(IC3A-C)") (class "Default")
      (node (ref "IC3") (pin "13") (pinfunction "C_13") (pintype "input"))
      (node (ref "R39") (pin "1") (pinfunction "1_1") (pintype "passive"))
      (node (ref "S5") (pin "11") (pinfunction "11_11") (pintype "passive"))
    )
    (net (code "47") (name "Net-(IC3A-D)") (class "Default")
      (node (ref "IC3") (pin "14") (pinfunction "D_14") (pintype "input"))
      (node (ref "R38") (pin "1") (pinfunction "1_1") (pintype "passive"))
      (node (ref "S5") (pin "12") (pinfunction "12_12") (pintype "passive"))
    )
    (net (code "48") (name "Net-(IC3A-E)") (class "Default")
      (node (ref "IC3") (pin "3") (pinfunction "E_3") (pintype "input"))
      (node (ref "R35") (pin "1") (pinfunction "1_1") (pintype "passive"))
      (node (ref "S5") (pin "13") (pinfunction "13_13") (pintype "passive"))
    )
    (net (code "49") (name "Net-(IC3A-F)") (class "Default")
      (node (ref "IC3") (pin "4") (pinfunction "F_4") (pintype "input"))
      (node (ref "R24") (pin "1") (pinfunction "1_1") (pintype "passive"))
      (node (ref "S5") (pin "14") (pinfunction "14_14") (pintype "passive"))
    )
    (net (code "50") (name "Net-(IC3A-G)") (class "Default")
      (node (ref "IC3") (pin "5") (pinfunction "G_5") (pintype "input"))
      (node (ref "R23") (pin "1") (pinfunction "1_1") (pintype "passive"))
      (node (ref "S5") (pin "15") (pinfunction "15_15") (pintype "passive"))
    )
    (net (code "51") (name "Net-(IC3A-H)") (class "Default")
      (node (ref "IC3") (pin "6") (pinfunction "H_6") (pintype "input"))
      (node (ref "R43") (pin "1") (pinfunction "1_1") (pintype "passive"))
      (node (ref "S5") (pin "16") (pinfunction "16_16") (pintype "passive"))
    )
    (net (code "52") (name "Net-(IC3A-QH)") (class "Default")
      (node (ref "IC3") (pin "9") (pinfunction "QH_9") (pintype "output"))
      (node (ref "R12") (pin "1") (pinfunction "1_1") (pintype "passive"))
    )
    (net (code "53") (name "Net-(LCD-POWER-Pad2)") (class "Default")
      (node (ref "LCD-POWER") (pin "2") (pinfunction "2_2") (pintype "passive"))
      (node (ref "R15") (pin "2") (pinfunction "2_2") (pintype "passive"))
    )
    (net (code "54") (name "Net-(LCD1-CONTR)") (class "Default")
      (node (ref "LCD1") (pin "3") (pinfunction "CONTR_3") (pintype "input"))
      (node (ref "LCD_POTI") (pin "1") (pinfunction "A_1") (pintype "passive"))
    )
    (net (code "55") (name "Net-(LCD1-E(SCLK))") (class "Default")
      (node (ref "LCD1") (pin "6") (pinfunction "E(SCLK)_6") (pintype "input"))
      (node (ref "R11") (pin "1") (pinfunction "1_1") (pintype "passive"))
      (node (ref "R14") (pin "2") (pinfunction "2_2") (pintype "passive"))
    )
    (net (code "56") (name "Net-(LCD1-LED+)") (class "Default")
      (node (ref "LCD1") (pin "17") (pinfunction "LED+_17") (pintype "passive"))
      (node (ref "R15") (pin "1") (pinfunction "1_1") (pintype "passive"))
    )
    (net (code "57") (name "Net-(LCD1-R{slash}W(SID))") (class "Default")
      (node (ref "LCD1") (pin "5") (pinfunction "R/W(SID)_5") (pintype "input"))
      (node (ref "R13") (pin "1") (pinfunction "1_1") (pintype "passive"))
      (node (ref "R16") (pin "2") (pinfunction "2_2") (pintype "passive"))
    )
    (net (code "58") (name "Net-(R1-Pad2)") (class "Default")
      (node (ref "R1") (pin "2") (pinfunction "2_2") (pintype "passive"))
      (node (ref "R3") (pin "2") (pinfunction "2_2") (pintype "passive"))
      (node (ref "S1") (pin "1") (pinfunction "1_1") (pintype "passive"))
      (node (ref "S1") (pin "2") (pinfunction "2_2") (pintype "passive"))
    )
    (net (code "59") (name "Net-(R2-Pad2)") (class "Default")
      (node (ref "R2") (pin "2") (pinfunction "2_2") (pintype "passive"))
      (node (ref "R4") (pin "2") (pinfunction "2_2") (pintype "passive"))
      (node (ref "S2") (pin "1") (pinfunction "1_1") (pintype "passive"))
      (node (ref "S2") (pin "2") (pinfunction "2_2") (pintype "passive"))
    )
    (net (code "60") (name "Net-(R6-Pad1)") (class "Default")
      (node (ref "R6") (pin "1") (pinfunction "1_1") (pintype "passive"))
      (node (ref "R9") (pin "1") (pinfunction "1_1") (pintype "passive"))
      (node (ref "S3") (pin "3") (pinfunction "3_3") (pintype "passive"))
      (node (ref "S3") (pin "4") (pinfunction "4_4") (pintype "passive"))
    )
    (net (code "61") (name "Net-(R10-Pad1)") (class "Default")
      (node (ref "R10") (pin "1") (pinfunction "1_1") (pintype "passive"))
      (node (ref "R7") (pin "1") (pinfunction "1_1") (pintype "passive"))
      (node (ref "S4") (pin "3") (pinfunction "3_3") (pintype "passive"))
      (node (ref "S4") (pin "4") (pinfunction "4_4") (pintype "passive"))
    )
    (net (code "62") (name "Net-(R18-Pad2)") (class "Default")
      (node (ref "R18") (pin "2") (pinfunction "2_2") (pintype "passive"))
      (node (ref "U$3") (pin "TRIM") (pinfunction "TRIM_TRIM") (pintype "bidirectional"))
    )
    (net (code "63") (name "Net-(RN1-RXD)") (class "Default")
      (node (ref "RN1") (pin "5") (pinfunction "RXD_5") (pintype "bidirectional"))
      (node (ref "RS232_BT") (pin "2") (pinfunction "2_2") (pintype "passive"))
    )
    (net (code "64") (name "Net-(RN1-TXD)") (class "Default")
      (node (ref "RN1") (pin "4") (pinfunction "TXD_4") (pintype "bidirectional"))
      (node (ref "RS232_BT") (pin "4") (pinfunction "4_4") (pintype "passive"))
    )
    (net (code "65") (name "Net-(U$3-PadREMOTE)") (class "Default")
      (node (ref "U$3") (pin "REMOTE") (pinfunction "REMOTE_REMOTE") (pintype "bidirectional"))
      (node (ref "UART_ROBO1") (pin "2") (pinfunction "2_2") (pintype "passive"))
    )
    (net (code "66") (name "Net-(V1-D)") (class "Default")
      (node (ref "R25") (pin "1") (pinfunction "1_1") (pintype "passive"))
      (node (ref "V1") (pin "3") (pinfunction "D_3") (pintype "passive"))
    )
    (net (code "67") (name "Net-(V2-D)") (class "Default")
      (node (ref "R26") (pin "1") (pinfunction "1_1") (pintype "passive"))
      (node (ref "V2") (pin "3") (pinfunction "D_3") (pintype "passive"))
    )
    (net (code "68") (name "Net-(V3-D)") (class "Default")
      (node (ref "R27") (pin "1") (pinfunction "1_1") (pintype "passive"))
      (node (ref "V3") (pin "3") (pinfunction "D_3") (pintype "passive"))
    )
    (net (code "69") (name "Net-(V4-D)") (class "Default")
      (node (ref "R28") (pin "1") (pinfunction "1_1") (pintype "passive"))
      (node (ref "V4") (pin "3") (pinfunction "D_3") (pintype "passive"))
    )
    (net (code "70") (name "Net-(V5-D)") (class "Default")
      (node (ref "R29") (pin "1") (pinfunction "1_1") (pintype "passive"))
      (node (ref "V5") (pin "3") (pinfunction "D_3") (pintype "passive"))
    )
    (net (code "71") (name "Net-(V6-D)") (class "Default")
      (node (ref "R30") (pin "1") (pinfunction "1_1") (pintype "passive"))
      (node (ref "V6") (pin "3") (pinfunction "D_3") (pintype "passive"))
    )
    (net (code "72") (name "Net-(V7-D)") (class "Default")
      (node (ref "R31") (pin "1") (pinfunction "1_1") (pintype "passive"))
      (node (ref "V7") (pin "3") (pinfunction "D_3") (pintype "passive"))
    )
    (net (code "73") (name "Net-(V8-D)") (class "Default")
      (node (ref "R32") (pin "1") (pinfunction "1_1") (pintype "passive"))
      (node (ref "V8") (pin "3") (pinfunction "D_3") (pintype "passive"))
    )
    (net (code "74") (name "PA0") (class "Default")
      (node (ref "IC1") (pin "37") (pinfunction "(PCINT0/ADC0)PA0_37") (pintype "bidirectional"))
      (node (ref "PORT_A") (pin "2") (pinfunction "2_2") (pintype "passive"))
      (node (ref "PORT_A2") (pin "1") (pinfunction "1_1") (pintype "passive"))
    )
    (net (code "75") (name "PA0_") (class "Default")
      (node (ref "IC4") (pin "13") (pinfunction "(PCINT0/AREF/ADC0)PA0_13") (pintype "bidirectional"))
      (node (ref "PORT_A1") (pin "2") (pinfunction "2_2") (pintype "passive"))
    )
    (net (code "76") (name "PA1") (class "Default")
      (node (ref "IC1") (pin "36") (pinfunction "(PCINT1/ADC1)PA1_36") (pintype "bidirectional"))
      (node (ref "PORT_A") (pin "3") (pinfunction "3_3") (pintype "passive"))
      (node (ref "PORT_A2") (pin "3") (pinfunction "3_3") (pintype "passive"))
    )
    (net (code "77") (name "PA1_") (class "Default")
      (node (ref "IC4") (pin "12") (pinfunction "(PCINT1/AIN0/ADC1)PA1_12") (pintype "bidirectional"))
      (node (ref "PORT_A1") (pin "1") (pinfunction "1_1") (pintype "passive"))
    )
    (net (code "78") (name "PA2") (class "Default")
      (node (ref "IC1") (pin "35") (pinfunction "(PCINT2/ADC2)PA2_35") (pintype "bidirectional"))
      (node (ref "PORT_A") (pin "4") (pinfunction "4_4") (pintype "passive"))
      (node (ref "PORT_A2") (pin "5") (pinfunction "5_5") (pintype "passive"))
    )
    (net (code "79") (name "PA2_") (class "Default")
      (node (ref "IC4") (pin "11") (pinfunction "(PCINT2/AIN1/ADC2)PA2_11") (pintype "bidirectional"))
      (node (ref "PORT_A1") (pin "4") (pinfunction "4_4") (pintype "passive"))
    )
    (net (code "80") (name "PA3") (class "Default")
      (node (ref "IC1") (pin "34") (pinfunction "(PCINT3/ADC3)PA3_34") (pintype "bidirectional"))
      (node (ref "PORT_A") (pin "5") (pinfunction "5_5") (pintype "passive"))
      (node (ref "PORT_A2") (pin "7") (pinfunction "7_7") (pintype "passive"))
    )
    (net (code "81") (name "PA3_") (class "Default")
      (node (ref "IC4") (pin "10") (pinfunction "(PCINT3/T0/ADC3)PA3_10") (pintype "bidirectional"))
      (node (ref "PORT_A1") (pin "3") (pinfunction "3_3") (pintype "passive"))
    )
    (net (code "82") (name "PA4_") (class "Default")
      (node (ref "IC4") (pin "9") (pinfunction "(PCINT4/T1/SCL/USCK/ADC4)PA4_9") (pintype "bidirectional"))
      (node (ref "PORT_A1") (pin "6") (pinfunction "6_6") (pintype "passive"))
    )
    (net (code "83") (name "PA5_") (class "Default")
      (node (ref "IC4") (pin "8") (pinfunction "(PCINT5/OC1B/MISO/DO/ADC5)PA5_8") (pintype "bidirectional"))
      (node (ref "PORT_A1") (pin "5") (pinfunction "5_5") (pintype "passive"))
    )
    (net (code "84") (name "PA6_") (class "Default")
      (node (ref "IC4") (pin "7") (pinfunction "(PCINT6/OC1A/SDA/MOSI/ADC6)PA6_7") (pintype "bidirectional"))
      (node (ref "PORT_A1") (pin "8") (pinfunction "8_8") (pintype "passive"))
    )
    (net (code "85") (name "PA7_") (class "Default")
      (node (ref "IC4") (pin "6") (pinfunction "(PCINT7/ICP/OC0B/ADC7)PA7_6") (pintype "bidirectional"))
      (node (ref "PORT_A1") (pin "7") (pinfunction "7_7") (pintype "passive"))
    )
    (net (code "86") (name "PB0") (class "Default")
      (node (ref "IC1") (pin "40") (pinfunction "(PCINT8/XCK0/T0)PB0_40") (pintype "bidirectional"))
      (node (ref "R1") (pin "1") (pinfunction "1_1") (pintype "passive"))
      (node (ref "V8") (pin "1") (pinfunction "G_1") (pintype "passive"))
    )
    (net (code "87") (name "PB0_") (class "Default")
      (node (ref "IC4") (pin "2") (pinfunction "(PCINT8/XTAL1/CLKI)PB0_2") (pintype "bidirectional"))
      (node (ref "PORT_A2") (pin "2") (pinfunction "2_2") (pintype "passive"))
    )
    (net (code "88") (name "PB1") (class "Default")
      (node (ref "IC1") (pin "41") (pinfunction "(PCINT9/CLKO/T1)PB1_41") (pintype "bidirectional"))
      (node (ref "R2") (pin "1") (pinfunction "1_1") (pintype "passive"))
      (node (ref "V7") (pin "1") (pinfunction "G_1") (pintype "passive"))
    )
    (net (code "89") (name "PB1_") (class "Default")
      (node (ref "IC4") (pin "3") (pinfunction "(PCINT9/XTAL2)PB1_3") (pintype "bidirectional"))
      (node (ref "PORT_A2") (pin "4") (pinfunction "4_4") (pintype "passive"))
    )
    (net (code "90") (name "PB2") (class "Default")
      (node (ref "IC1") (pin "42") (pinfunction "(PCINT10/INT2/AIN0)PB2_42") (pintype "bidirectional"))
      (node (ref "R9") (pin "2") (pinfunction "2_2") (pintype "passive"))
      (node (ref "V6") (pin "1") (pinfunction "G_1") (pintype "passive"))
    )
    (net (code "91") (name "PB2_") (class "Default")
      (node (ref "IC4") (pin "5") (pinfunction "(PCINT10/INT0/OC0A/CKOUT)PB2_5") (pintype "bidirectional"))
      (node (ref "PORT_A2") (pin "6") (pinfunction "6_6") (pintype "passive"))
    )
    (net (code "92") (name "PB3") (class "Default")
      (node (ref "IC1") (pin "43") (pinfunction "(PCINT11/OC0A/AIN1)PB3_43") (pintype "bidirectional"))
      (node (ref "R10") (pin "2") (pinfunction "2_2") (pintype "passive"))
      (node (ref "V5") (pin "1") (pinfunction "G_1") (pintype "passive"))
    )
    (net (code "93") (name "PB3_") (class "Default")
      (node (ref "IC4") (pin "4") (pinfunction "(PCINT11/RESET/DW)PB3_4") (pintype "bidirectional"))
      (node (ref "PORT_A2") (pin "8") (pinfunction "8_8") (pintype "passive"))
    )
    (net (code "94") (name "PB4") (class "Default")
      (node (ref "IC1") (pin "44") (pinfunction "(PCINT12/OC0B/~{SS})PB4_44") (pintype "bidirectional"))
      (node (ref "V4") (pin "1") (pinfunction "G_1") (pintype "passive"))
    )
    (net (code "95") (name "PB5") (class "Default")
      (node (ref "IC1") (pin "1") (pinfunction "(PCINT13/MOSI)PB5_1") (pintype "bidirectional"))
      (node (ref "V3") (pin "1") (pinfunction "G_1") (pintype "passive"))
    )
    (net (code "96") (name "PB6") (class "Default")
      (node (ref "IC1") (pin "2") (pinfunction "(PCINT14/MISO)PB6_2") (pintype "bidirectional"))
      (node (ref "V2") (pin "1") (pinfunction "G_1") (pintype "passive"))
    )
    (net (code "97") (name "PB7") (class "Default")
      (node (ref "IC1") (pin "3") (pinfunction "(PCINT15/SCK)PB7_3") (pintype "bidirectional"))
      (node (ref "V1") (pin "1") (pinfunction "G_1") (pintype "passive"))
    )
    (net (code "98") (name "PD2") (class "Default")
      (node (ref "IC1") (pin "11") (pinfunction "(PCINT26/INT0)PD2_11") (pintype "bidirectional"))
      (node (ref "PORT_D") (pin "4") (pinfunction "4_4") (pintype "passive"))
      (node (ref "UART_ROBO") (pin "2") (pinfunction "2_2") (pintype "passive"))
    )
    (net (code "99") (name "PD3") (class "Default")
      (node (ref "IC1") (pin "12") (pinfunction "(PCINT27/INT1)PD3_12") (pintype "bidirectional"))
      (node (ref "PORT_D") (pin "5") (pinfunction "5_5") (pintype "passive"))
      (node (ref "UART_ROBO") (pin "3") (pinfunction "3_3") (pintype "passive"))
    )
    (net (code "100") (name "VCC") (class "Default")
      (node (ref "0_OHM_A") (pin "1") (pinfunction "1_1") (pintype "passive"))
      (node (ref "5V_DC") (pin "OUT") (pinfunction "OUT_OUT") (pintype "passive"))
      (node (ref "C10") (pin "+") (pinfunction "+_+") (pintype "passive"))
      (node (ref "C11") (pin "1") (pinfunction "1_1") (pintype "passive"))
      (node (ref "C12") (pin "+") (pinfunction "+_+") (pintype "passive"))
      (node (ref "C6") (pin "1") (pinfunction "1_1") (pintype "passive"))
      (node (ref "D2") (pin "A") (pinfunction "A_A") (pintype "passive"))
      (node (ref "F2") (pin "2") (pinfunction "2_2") (pintype "passive"))
      (node (ref "L1") (pin "1") (pinfunction "1_1") (pintype "passive"))
      (node (ref "LCD-POWER") (pin "1") (pinfunction "1_1") (pintype "passive"))
      (node (ref "LED-POWER") (pin "1") (pinfunction "1_1") (pintype "passive"))
      (node (ref "R8") (pin "2") (pinfunction "2_2") (pintype "passive"))
      (node (ref "RN1") (pin "3") (pinfunction "VCC_3") (pintype "bidirectional"))
      (node (ref "S1") (pin "3") (pinfunction "3_3") (pintype "passive"))
      (node (ref "S1") (pin "4") (pinfunction "4_4") (pintype "passive"))
      (node (ref "S2") (pin "3") (pinfunction "3_3") (pintype "passive"))
      (node (ref "S2") (pin "4") (pinfunction "4_4") (pintype "passive"))
      (node (ref "S3") (pin "1") (pinfunction "1_1") (pintype "passive"))
      (node (ref "S3") (pin "2") (pinfunction "2_2") (pintype "passive"))
      (node (ref "S4") (pin "1") (pinfunction "1_1") (pintype "passive"))
      (node (ref "S4") (pin "2") (pinfunction "2_2") (pintype "passive"))
      (node (ref "VCC") (pin "MP") (pinfunction "MP_MP") (pintype "passive"))
    )
    (net (code "101") (name "unconnected-(IC3A-~{QH}-Pad7)") (class "Default")
      (node (ref "IC3") (pin "7") (pinfunction "~{QH}_7") (pintype "output"))
    )
    (net (code "102") (name "unconnected-(JTAG-Pad6)") (class "Default")
      (node (ref "JTAG") (pin "6") (pinfunction "6_6") (pintype "passive"))
    )
    (net (code "103") (name "unconnected-(JTAG-Pad7)") (class "Default")
      (node (ref "JTAG") (pin "7") (pinfunction "7_7") (pintype "passive"))
    )
    (net (code "104") (name "unconnected-(JTAG-Pad8)") (class "Default")
      (node (ref "JTAG") (pin "8") (pinfunction "8_8") (pintype "passive"))
    )
    (net (code "105") (name "unconnected-(LCD1-D0(SOD)-Pad7)") (class "Default")
      (node (ref "LCD1") (pin "7") (pinfunction "D0(SOD)_7") (pintype "no_connect"))
    )
    (net (code "106") (name "unconnected-(LCD1-D1-Pad8)") (class "Default")
      (node (ref "LCD1") (pin "8") (pinfunction "D1_8") (pintype "no_connect"))
    )
    (net (code "107") (name "unconnected-(LCD1-D2-Pad9)") (class "Default")
      (node (ref "LCD1") (pin "9") (pinfunction "D2_9") (pintype "no_connect"))
    )
    (net (code "108") (name "unconnected-(LCD1-D3-Pad10)") (class "Default")
      (node (ref "LCD1") (pin "10") (pinfunction "D3_10") (pintype "no_connect"))
    )
    (net (code "109") (name "unconnected-(LCD1-D4-Pad11)") (class "Default")
      (node (ref "LCD1") (pin "11") (pinfunction "D4_11") (pintype "no_connect"))
    )
    (net (code "110") (name "unconnected-(LCD1-D5-Pad12)") (class "Default")
      (node (ref "LCD1") (pin "12") (pinfunction "D5_12") (pintype "no_connect"))
    )
    (net (code "111") (name "unconnected-(LCD1-D6-Pad13)") (class "Default")
      (node (ref "LCD1") (pin "13") (pinfunction "D6_13") (pintype "no_connect"))
    )
    (net (code "112") (name "unconnected-(LCD1-D7-Pad14)") (class "Default")
      (node (ref "LCD1") (pin "14") (pinfunction "D7_14") (pintype "no_connect"))
    )
    (net (code "113") (name "unconnected-(LCD1-NC-Pad15)") (class "Default")
      (node (ref "LCD1") (pin "15") (pinfunction "NC_15") (pintype "no_connect"))
    )
    (net (code "114") (name "unconnected-(LCD1-RESET-Pad16)") (class "Default")
      (node (ref "LCD1") (pin "16") (pinfunction "RESET_16") (pintype "no_connect"))
    )
    (net (code "115") (name "unconnected-(PORT_A1-Pad9)") (class "Default")
      (node (ref "PORT_A1") (pin "9") (pinfunction "9_9") (pintype "passive"))
    )
    (net (code "116") (name "unconnected-(PORT_A1-Pad10)") (class "Default")
      (node (ref "PORT_A1") (pin "10") (pinfunction "10_10") (pintype "passive"))
    )
    (net (code "117") (name "unconnected-(PORT_A2-Pad9)") (class "Default")
      (node (ref "PORT_A2") (pin "9") (pinfunction "9_9") (pintype "passive"))
    )
    (net (code "118") (name "unconnected-(PORT_A2-Pad10)") (class "Default")
      (node (ref "PORT_A2") (pin "10") (pinfunction "10_10") (pintype "passive"))
    )
    (net (code "119") (name "unconnected-(RN1-CTS_I-Pad2)") (class "Default")
      (node (ref "RN1") (pin "2") (pinfunction "CTS_I_2") (pintype "bidirectional"))
    )
    (net (code "120") (name "unconnected-(RN1-RTS_O-Pad6)") (class "Default")
      (node (ref "RN1") (pin "6") (pinfunction "RTS_O_6") (pintype "bidirectional"))
    )
    (net (code "121") (name "unconnected-(U$1-Pad2)") (class "Default")
      (node (ref "U$1") (pin "2") (pinfunction "2_2") (pintype "no_connect"))
    )
    (net (code "122") (name "unconnected-(U$1-Pad3)") (class "Default")
      (node (ref "U$1") (pin "3") (pinfunction "3_3") (pintype "no_connect"))
    )
    (net (code "123") (name "unconnected-(U$1-Pad4)") (class "Default")
      (node (ref "U$1") (pin "4") (pinfunction "4_4") (pintype "no_connect"))
    )
  )
)
